# PsOne_LED_Driver.net
KiCad netlist of a schematic drawn in EAGLE
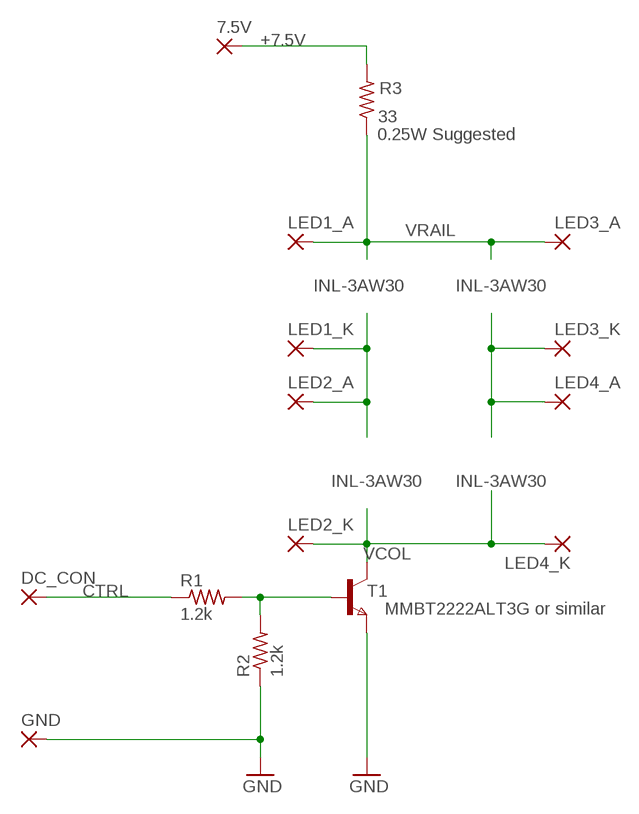
[diagram p0: schematic, sheet 1]

(export (version "E")
  (design (tool "Eeschema 10.0.6"))
  (components
    (comp (ref "7.5V")
      (value "SMD5")
      (footprint "eagle-import:SMD2,54-5,08")
      (libsource (lib "eagle-import") (part "SMD5"))
    )
    (comp (ref "DC_CON")
      (value "SMD5")
      (footprint "eagle-import:SMD2,54-5,08")
      (libsource (lib "eagle-import") (part "SMD5"))
    )
    (comp (ref "GND")
      (value "SMD5")
      (footprint "eagle-import:SMD2,54-5,08")
      (libsource (lib "eagle-import") (part "SMD5"))
    )
    (comp (ref "LED1_A")
      (value "SMD2")
      (footprint "eagle-import:SMD1,27-2,54")
      (libsource (lib "eagle-import") (part "SMD2"))
    )
    (comp (ref "LED1_K")
      (value "SMD2")
      (footprint "eagle-import:SMD1,27-2,54")
      (libsource (lib "eagle-import") (part "SMD2"))
    )
    (comp (ref "LED2_A")
      (value "SMD2")
      (footprint "eagle-import:SMD1,27-2,54")
      (libsource (lib "eagle-import") (part "SMD2"))
    )
    (comp (ref "LED2_K")
      (value "SMD2")
      (footprint "eagle-import:SMD1,27-2,54")
      (libsource (lib "eagle-import") (part "SMD2"))
    )
    (comp (ref "LED3_A")
      (value "SMD2")
      (footprint "eagle-import:SMD1,27-2,54")
      (libsource (lib "eagle-import") (part "SMD2"))
    )
    (comp (ref "LED3_K")
      (value "SMD2")
      (footprint "eagle-import:SMD1,27-2,54")
      (libsource (lib "eagle-import") (part "SMD2"))
    )
    (comp (ref "LED4_A")
      (value "SMD2")
      (footprint "eagle-import:SMD1,27-2,54")
      (libsource (lib "eagle-import") (part "SMD2"))
    )
    (comp (ref "LED4_K")
      (value "SMD2")
      (footprint "eagle-import:SMD1,27-2,54")
      (libsource (lib "eagle-import") (part "SMD2"))
    )
    (comp (ref "R1")
      (value "1.2k")
      (footprint "eagle-import:R0603")
      (libsource (lib "eagle-import") (part "R-US_R0603"))
    )
    (comp (ref "R2")
      (value "1.2k")
      (footprint "eagle-import:R0603")
      (libsource (lib "eagle-import") (part "R-US_R0603"))
    )
    (comp (ref "R3")
      (value "33")
      (footprint "eagle-import:R1206")
      (libsource (lib "eagle-import") (part "R-US_R1206"))
    )
    (comp (ref "T1")
      (value "NPNSOT23")
      (footprint "eagle-import:SOT-23")
      (fields (field (name "MPN") "DSS20201L-7"))
      (libsource (lib "eagle-import") (part "NPNSOT23"))
    )
  )
  (nets
    (net (code "1") (name "/+7.5V") (class "Default")
      (node (ref "7.5V") (pin "1") (pinfunction "P_1") (pintype "passive"))
      (node (ref "R3") (pin "2") (pinfunction "2_2") (pintype "passive"))
    )
    (net (code "2") (name "/CTRL") (class "Default")
      (node (ref "DC_CON") (pin "1") (pinfunction "P_1") (pintype "passive"))
      (node (ref "R1") (pin "1") (pinfunction "1_1") (pintype "passive"))
    )
    (net (code "3") (name "/VCOL") (class "Default")
      (node (ref "LED2_K") (pin "1") (pinfunction "P_1") (pintype "passive"))
      (node (ref "LED4_K") (pin "1") (pinfunction "P_1") (pintype "passive"))
      (node (ref "T1") (pin "1") (pinfunction "C_1") (pintype "passive"))
    )
    (net (code "4") (name "/VRAIL") (class "Default")
      (node (ref "LED1_A") (pin "1") (pinfunction "P_1") (pintype "passive"))
      (node (ref "LED3_A") (pin "1") (pinfunction "P_1") (pintype "passive"))
      (node (ref "R3") (pin "1") (pinfunction "1_1") (pintype "passive"))
    )
    (net (code "5") (name "GND") (class "Default")
      (node (ref "GND") (pin "1") (pinfunction "P_1") (pintype "passive"))
      (node (ref "R2") (pin "1") (pinfunction "1_1") (pintype "passive"))
      (node (ref "T1") (pin "2") (pinfunction "E_2") (pintype "passive"))
    )
    (net (code "6") (name "Net-(LED1_K-P)") (class "Default")
      (node (ref "LED1_K") (pin "1") (pinfunction "P_1") (pintype "passive"))
      (node (ref "LED2_A") (pin "1") (pinfunction "P_1") (pintype "passive"))
    )
    (net (code "7") (name "Net-(LED3_K-P)") (class "Default")
      (node (ref "LED3_K") (pin "1") (pinfunction "P_1") (pintype "passive"))
      (node (ref "LED4_A") (pin "1") (pinfunction "P_1") (pintype "passive"))
    )
    (net (code "8") (name "Net-(T1-B)") (class "Default")
      (node (ref "R1") (pin "2") (pinfunction "2_2") (pintype "passive"))
      (node (ref "R2") (pin "2") (pinfunction "2_2") (pintype "passive"))
      (node (ref "T1") (pin "3") (pinfunction "B_3") (pintype "passive"))
    )
  )
)
